# 3.net
KiCad netlist of a schematic drawn in Altium Designer
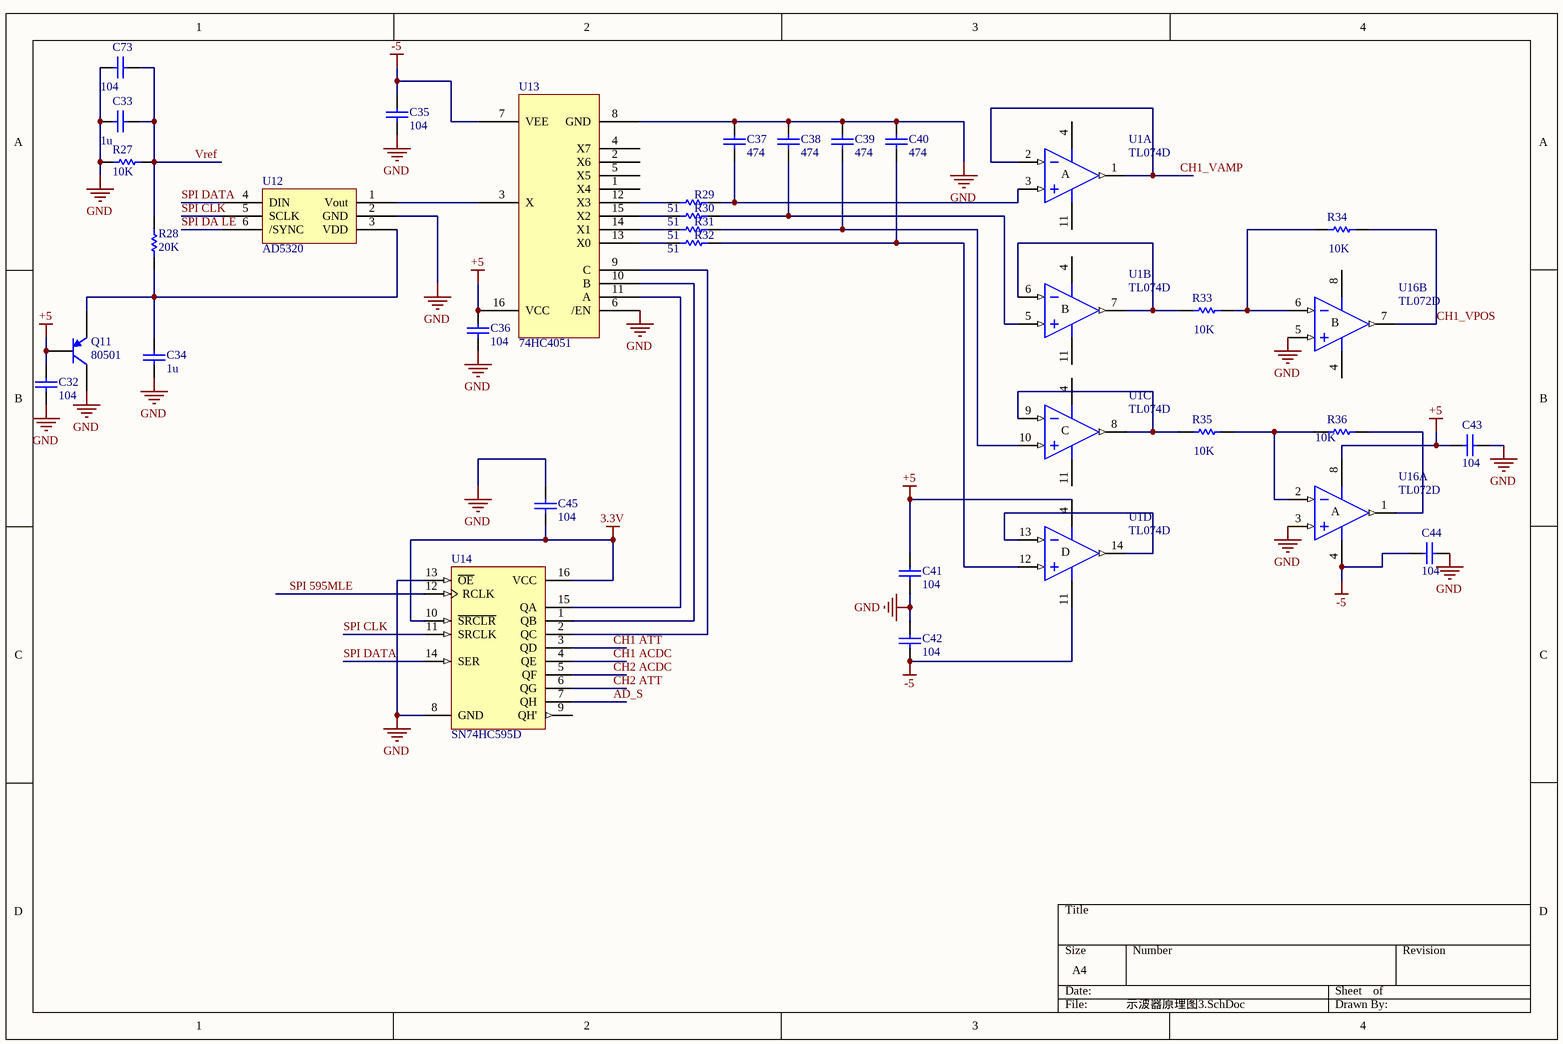
[diagram p0: 示波器原理图3.SchDoc]

(export (version "E")
  (design (tool "Eeschema 10.0.6"))
  (components
    (comp (ref "C32")
      (value "104")
      (footprint "PCBComponent_1")
      (description "Capacitor")
      (fields (field (name "PUBLISHER") "Altium Limited"))
      (libsource (lib "Miscellaneous Devices") (part "Cap"))
    )
    (comp (ref "C33")
      (value "1u")
      (footprint "PCBComponent_1")
      (description "Capacitor")
      (fields (field (name "PUBLISHER") "Altium Limited"))
      (libsource (lib "Miscellaneous Devices") (part "Cap"))
    )
    (comp (ref "C34")
      (value "1u")
      (footprint "PCBComponent_1")
      (description "Capacitor")
      (fields (field (name "PUBLISHER") "Altium Limited"))
      (libsource (lib "Miscellaneous Devices") (part "Cap"))
    )
    (comp (ref "C35")
      (value "104")
      (footprint "PCBComponent_1")
      (description "Capacitor")
      (fields (field (name "PUBLISHER") "Altium Limited"))
      (libsource (lib "Miscellaneous Devices") (part "Cap"))
    )
    (comp (ref "C36")
      (value "104")
      (footprint "PCBComponent_1")
      (description "Capacitor")
      (fields (field (name "PUBLISHER") "Altium Limited"))
      (libsource (lib "Miscellaneous Devices") (part "Cap"))
    )
    (comp (ref "C37")
      (value "474")
      (footprint "PCBComponent_1")
      (description "Capacitor")
      (fields (field (name "PUBLISHER") "Altium Limited"))
      (libsource (lib "Miscellaneous Devices") (part "Cap"))
    )
    (comp (ref "C38")
      (value "474")
      (footprint "PCBComponent_1")
      (description "Capacitor")
      (fields (field (name "PUBLISHER") "Altium Limited"))
      (libsource (lib "Miscellaneous Devices") (part "Cap"))
    )
    (comp (ref "C39")
      (value "474")
      (footprint "PCBComponent_1")
      (description "Capacitor")
      (fields (field (name "PUBLISHER") "Altium Limited"))
      (libsource (lib "Miscellaneous Devices") (part "Cap"))
    )
    (comp (ref "C40")
      (value "474")
      (footprint "PCBComponent_1")
      (description "Capacitor")
      (fields (field (name "PUBLISHER") "Altium Limited"))
      (libsource (lib "Miscellaneous Devices") (part "Cap"))
    )
    (comp (ref "C41")
      (value "104")
      (footprint "PCBComponent_1")
      (description "Capacitor")
      (fields (field (name "PUBLISHER") "Altium Limited"))
      (libsource (lib "Miscellaneous Devices") (part "Cap"))
    )
    (comp (ref "C42")
      (value "104")
      (footprint "PCBComponent_1")
      (description "Capacitor")
      (fields (field (name "PUBLISHER") "Altium Limited"))
      (libsource (lib "Miscellaneous Devices") (part "Cap"))
    )
    (comp (ref "C43")
      (value "104")
      (footprint "PCBComponent_1")
      (description "Capacitor")
      (fields (field (name "PUBLISHER") "Altium Limited"))
      (libsource (lib "Miscellaneous Devices") (part "Cap"))
    )
    (comp (ref "C44")
      (value "104")
      (footprint "PCBComponent_1")
      (description "Capacitor")
      (fields (field (name "PUBLISHER") "Altium Limited"))
      (libsource (lib "Miscellaneous Devices") (part "Cap"))
    )
    (comp (ref "C45")
      (value "104")
      (footprint "PCBComponent_1")
      (description "Capacitor")
      (fields (field (name "PUBLISHER") "Altium Limited"))
      (libsource (lib "Miscellaneous Devices") (part "Cap"))
    )
    (comp (ref "C73")
      (value "104")
      (footprint "PCBComponent_1")
      (description "Capacitor")
      (fields (field (name "PUBLISHER") "Altium Limited"))
      (libsource (lib "Miscellaneous Devices") (part "Cap"))
    )
    (comp (ref "Q11")
      (value "80501")
      (footprint "三极管贴片:PCBComponent_1")
      (description "PNP General Purpose Amplifier")
      (fields (field (name "PUBLISHER") "Altium Limited"))
      (libsource (lib "Miscellaneous Devices") (part "2N3906"))
    )
    (comp (ref "R27")
      (value "10K")
      (footprint "PCBComponent_1")
      (description "Resistor")
      (fields (field (name "PUBLISHER") "Altium Limited"))
      (libsource (lib "Miscellaneous Devices") (part "Res1"))
    )
    (comp (ref "R28")
      (value "20K")
      (footprint "PCBComponent_1")
      (description "Resistor")
      (fields (field (name "PUBLISHER") "Altium Limited"))
      (libsource (lib "Miscellaneous Devices") (part "Res1"))
    )
    (comp (ref "R29")
      (value "51")
      (footprint "2012[0805]")
      (description "Semiconductor Resistor")
      (fields (field (name "PUBLISHER") "Altium Limited"))
      (libsource (lib "Miscellaneous Devices") (part "Res Semi"))
    )
    (comp (ref "R30")
      (value "51")
      (footprint "2012[0805]")
      (description "Semiconductor Resistor")
      (fields (field (name "PUBLISHER") "Altium Limited"))
      (libsource (lib "Miscellaneous Devices") (part "Res Semi"))
    )
    (comp (ref "R31")
      (value "51")
      (footprint "2012[0805]")
      (description "Semiconductor Resistor")
      (fields (field (name "PUBLISHER") "Altium Limited"))
      (libsource (lib "Miscellaneous Devices") (part "Res Semi"))
    )
    (comp (ref "R32")
      (value "51")
      (footprint "2012[0805]")
      (description "Semiconductor Resistor")
      (fields (field (name "PUBLISHER") "Altium Limited"))
      (libsource (lib "Miscellaneous Devices") (part "Res Semi"))
    )
    (comp (ref "R33")
      (value "10K")
      (footprint "2012[0805]")
      (description "Semiconductor Resistor")
      (fields (field (name "PUBLISHER") "Altium Limited"))
      (libsource (lib "Miscellaneous Devices") (part "Res Semi"))
    )
    (comp (ref "R34")
      (value "10K")
      (footprint "2012[0805]")
      (description "Semiconductor Resistor")
      (fields (field (name "PUBLISHER") "Altium Limited"))
      (libsource (lib "Miscellaneous Devices") (part "Res Semi"))
    )
    (comp (ref "R35")
      (value "10K")
      (footprint "2012[0805]")
      (description "Semiconductor Resistor")
      (fields (field (name "PUBLISHER") "Altium Limited"))
      (libsource (lib "Miscellaneous Devices") (part "Res Semi"))
    )
    (comp (ref "R36")
      (value "10K")
      (footprint "2012[0805]")
      (description "Semiconductor Resistor")
      (fields (field (name "PUBLISHER") "Altium Limited"))
      (libsource (lib "Miscellaneous Devices") (part "Res Semi"))
    )
    (comp (ref "U1")
      (value "TL074D")
      (footprint "SOP127P600X175-14N")
      (description "Low-Noise JFET-Input Operational Amplifier")
      (fields (field (name "PUBLISHER") "Altium Limited"))
      (libsource (lib "TI Operational Amplifier") (part "TL074D"))
    )
    (comp (ref "U12")
      (value "AD5320")
      (footprint "SOT86P280X110-6N")
      (libsource (lib "AD5320") (part "Component_1"))
    )
    (comp (ref "U13")
      (value "74HC4051")
      (footprint "SOP127P600X175-16N")
      (libsource (lib "74HC4051") (part "Component_1"))
    )
    (comp (ref "U14")
      (value "SN74HC595D")
      (footprint "SOP127P600X175-16N")
      (description "8-Bit Shift Register with 3-State Output Registers")
      (fields (field (name "PUBLISHER") "Altium Limited"))
      (libsource (lib "TI Logic Register") (part "SN74HC595D"))
    )
    (comp (ref "U16")
      (value "TL072D")
      (footprint "SOP127P600X175-8N")
      (description "Low-Noise JFET-Input Operational Amplifier")
      (fields (field (name "PUBLISHER") "Altium Limited"))
      (libsource (lib "TI Operational Amplifier") (part "TL072D"))
    )
  )
  (nets
    (net (code "1") (name "+5") (class "Default")
      (node (ref "C32") (pin "2") (pinfunction "2_2") (pintype "passive"))
      (node (ref "C36") (pin "2") (pinfunction "2_2") (pintype "passive"))
      (node (ref "C41") (pin "1") (pinfunction "1_1") (pintype "passive"))
      (node (ref "C43") (pin "1") (pinfunction "1_1") (pintype "passive"))
      (node (ref "Q11") (pin "2") (pinfunction "B_2") (pintype "passive"))
      (node (ref "U1") (pin "4") (pinfunction "V+_4") (pintype "power_in"))
      (node (ref "U13") (pin "16") (pinfunction "VCC_16") (pintype "passive"))
      (node (ref "U16") (pin "8") (pinfunction "V+_8") (pintype "power_in"))
    )
    (net (code "2") (name "-5") (class "Default")
      (node (ref "C35") (pin "2") (pinfunction "2_2") (pintype "passive"))
      (node (ref "C42") (pin "2") (pinfunction "2_2") (pintype "passive"))
      (node (ref "C44") (pin "1") (pinfunction "1_1") (pintype "passive"))
      (node (ref "U1") (pin "11") (pinfunction "V-_11") (pintype "power_in"))
      (node (ref "U13") (pin "7") (pinfunction "VEE_7") (pintype "passive"))
      (node (ref "U16") (pin "4") (pinfunction "V-_4") (pintype "power_in"))
    )
    (net (code "3") (name "/AD_S") (class "Default")
      (node (ref "U14") (pin "7") (pinfunction "QH_7") (pintype "tri_state"))
    )
    (net (code "4") (name "/CH1 ACDC") (class "Default")
      (node (ref "U14") (pin "4") (pinfunction "QE_4") (pintype "tri_state"))
    )
    (net (code "5") (name "/CH1 ATT") (class "Default")
      (node (ref "U14") (pin "3") (pinfunction "QD_3") (pintype "tri_state"))
    )
    (net (code "6") (name "/CH1_VAMP") (class "Default")
      (node (ref "U1") (pin "1") (pinfunction "OUT_1") (pintype "output"))
      (node (ref "U1") (pin "2") (pinfunction "IN-_2") (pintype "input"))
    )
    (net (code "7") (name "/CH1_VPOS") (class "Default")
      (node (ref "R34") (pin "2") (pinfunction "2_2") (pintype "passive"))
      (node (ref "U16") (pin "7") (pinfunction "OUT_7") (pintype "output"))
    )
    (net (code "8") (name "/CH2 ACDC") (class "Default")
      (node (ref "U14") (pin "5") (pinfunction "QF_5") (pintype "tri_state"))
    )
    (net (code "9") (name "/CH2 ATT") (class "Default")
      (node (ref "U14") (pin "6") (pinfunction "QG_6") (pintype "tri_state"))
    )
    (net (code "10") (name "/SPI 595MLE") (class "Default")
      (node (ref "U14") (pin "12") (pinfunction "RCLK_12") (pintype "input"))
    )
    (net (code "11") (name "/SPI CLK") (class "Default")
      (node (ref "U12") (pin "5") (pinfunction "SCLK_5") (pintype "passive"))
      (node (ref "U14") (pin "11") (pinfunction "SRCLK_11") (pintype "input"))
    )
    (net (code "12") (name "/SPI DA LE") (class "Default")
      (node (ref "U12") (pin "6") (pinfunction "/SYNC_6") (pintype "passive"))
    )
    (net (code "13") (name "/SPI DATA") (class "Default")
      (node (ref "U12") (pin "4") (pinfunction "DIN_4") (pintype "passive"))
      (node (ref "U14") (pin "14") (pinfunction "SER_14") (pintype "input"))
    )
    (net (code "14") (name "/Vref") (class "Default")
      (node (ref "C33") (pin "2") (pinfunction "2_2") (pintype "passive"))
      (node (ref "C73") (pin "2") (pinfunction "2_2") (pintype "passive"))
      (node (ref "R27") (pin "1") (pinfunction "1_1") (pintype "passive"))
      (node (ref "R28") (pin "1") (pinfunction "1_1") (pintype "passive"))
    )
    (net (code "15") (name "3.3V") (class "Default")
      (node (ref "C45") (pin "1") (pinfunction "1_1") (pintype "passive"))
      (node (ref "U14") (pin "10") (pinfunction "~{SRCLR}_10") (pintype "input"))
      (node (ref "U14") (pin "16") (pinfunction "VCC_16") (pintype "power_in"))
    )
    (net (code "16") (name "GND") (class "Default")
      (node (ref "C32") (pin "1") (pinfunction "1_1") (pintype "passive"))
      (node (ref "C33") (pin "1") (pinfunction "1_1") (pintype "passive"))
      (node (ref "C34") (pin "1") (pinfunction "1_1") (pintype "passive"))
      (node (ref "C35") (pin "1") (pinfunction "1_1") (pintype "passive"))
      (node (ref "C36") (pin "1") (pinfunction "1_1") (pintype "passive"))
      (node (ref "C37") (pin "2") (pinfunction "2_2") (pintype "passive"))
      (node (ref "C38") (pin "2") (pinfunction "2_2") (pintype "passive"))
      (node (ref "C39") (pin "2") (pinfunction "2_2") (pintype "passive"))
      (node (ref "C40") (pin "2") (pinfunction "2_2") (pintype "passive"))
      (node (ref "C41") (pin "2") (pinfunction "2_2") (pintype "passive"))
      (node (ref "C42") (pin "1") (pinfunction "1_1") (pintype "passive"))
      (node (ref "C43") (pin "2") (pinfunction "2_2") (pintype "passive"))
      (node (ref "C44") (pin "2") (pinfunction "2_2") (pintype "passive"))
      (node (ref "C45") (pin "2") (pinfunction "2_2") (pintype "passive"))
      (node (ref "C73") (pin "1") (pinfunction "1_1") (pintype "passive"))
      (node (ref "Q11") (pin "3") (pinfunction "C_3") (pintype "passive"))
      (node (ref "R27") (pin "2") (pinfunction "2_2") (pintype "passive"))
      (node (ref "U12") (pin "2") (pinfunction "GND_2") (pintype "passive"))
      (node (ref "U13") (pin "6") (pinfunction "/EN_6") (pintype "passive"))
      (node (ref "U13") (pin "8") (pinfunction "GND_8") (pintype "passive"))
      (node (ref "U14") (pin "13") (pinfunction "~{OE}_13") (pintype "input"))
      (node (ref "U14") (pin "8") (pinfunction "GND_8") (pintype "power_in"))
      (node (ref "U16") (pin "3") (pinfunction "IN+_3") (pintype "input"))
      (node (ref "U16") (pin "5") (pinfunction "IN+_5") (pintype "input"))
    )
    (net (code "17") (name "Net-(Q11-E)") (class "Default")
      (node (ref "C34") (pin "2") (pinfunction "2_2") (pintype "passive"))
      (node (ref "Q11") (pin "1") (pinfunction "E_1") (pintype "passive"))
      (node (ref "R28") (pin "2") (pinfunction "2_2") (pintype "passive"))
      (node (ref "U12") (pin "3") (pinfunction "VDD_3") (pintype "passive"))
    )
    (net (code "18") (name "Net-(U1A-IN+)") (class "Default")
      (node (ref "C37") (pin "1") (pinfunction "1_1") (pintype "passive"))
      (node (ref "R29") (pin "2") (pinfunction "2_2") (pintype "passive"))
      (node (ref "U1") (pin "3") (pinfunction "IN+_3") (pintype "input"))
    )
    (net (code "19") (name "Net-(U1B-IN+)") (class "Default")
      (node (ref "C38") (pin "1") (pinfunction "1_1") (pintype "passive"))
      (node (ref "R30") (pin "2") (pinfunction "2_2") (pintype "passive"))
      (node (ref "U1") (pin "5") (pinfunction "IN+_5") (pintype "input"))
    )
    (net (code "20") (name "Net-(U1B-IN-)") (class "Default")
      (node (ref "R33") (pin "1") (pinfunction "1_1") (pintype "passive"))
      (node (ref "U1") (pin "6") (pinfunction "IN-_6") (pintype "input"))
      (node (ref "U1") (pin "7") (pinfunction "OUT_7") (pintype "output"))
    )
    (net (code "21") (name "Net-(U1C-IN+)") (class "Default")
      (node (ref "C39") (pin "1") (pinfunction "1_1") (pintype "passive"))
      (node (ref "R31") (pin "2") (pinfunction "2_2") (pintype "passive"))
      (node (ref "U1") (pin "10") (pinfunction "IN+_10") (pintype "input"))
    )
    (net (code "22") (name "Net-(U1C-IN-)") (class "Default")
      (node (ref "R35") (pin "1") (pinfunction "1_1") (pintype "passive"))
      (node (ref "U1") (pin "8") (pinfunction "OUT_8") (pintype "output"))
      (node (ref "U1") (pin "9") (pinfunction "IN-_9") (pintype "input"))
    )
    (net (code "23") (name "Net-(U1D-IN+)") (class "Default")
      (node (ref "C40") (pin "1") (pinfunction "1_1") (pintype "passive"))
      (node (ref "R32") (pin "2") (pinfunction "2_2") (pintype "passive"))
      (node (ref "U1") (pin "12") (pinfunction "IN+_12") (pintype "input"))
    )
    (net (code "24") (name "Net-(U1D-IN-)") (class "Default")
      (node (ref "U1") (pin "13") (pinfunction "IN-_13") (pintype "input"))
      (node (ref "U1") (pin "14") (pinfunction "OUT_14") (pintype "output"))
    )
    (net (code "25") (name "Net-(U12-Vout)") (class "Default")
      (node (ref "U12") (pin "1") (pinfunction "Vout_1") (pintype "passive"))
      (node (ref "U13") (pin "3") (pinfunction "X_3") (pintype "passive"))
    )
    (net (code "26") (name "Net-(U13-A)") (class "Default")
      (node (ref "U13") (pin "11") (pinfunction "A_11") (pintype "passive"))
      (node (ref "U14") (pin "15") (pinfunction "QA_15") (pintype "tri_state"))
    )
    (net (code "27") (name "Net-(U13-B)") (class "Default")
      (node (ref "U13") (pin "10") (pinfunction "B_10") (pintype "passive"))
      (node (ref "U14") (pin "1") (pinfunction "QB_1") (pintype "tri_state"))
    )
    (net (code "28") (name "Net-(U13-C)") (class "Default")
      (node (ref "U13") (pin "9") (pinfunction "C_9") (pintype "passive"))
      (node (ref "U14") (pin "2") (pinfunction "QC_2") (pintype "tri_state"))
    )
    (net (code "29") (name "Net-(U13-X0)") (class "Default")
      (node (ref "R32") (pin "1") (pinfunction "1_1") (pintype "passive"))
      (node (ref "U13") (pin "13") (pinfunction "X0_13") (pintype "passive"))
    )
    (net (code "30") (name "Net-(U13-X1)") (class "Default")
      (node (ref "R31") (pin "1") (pinfunction "1_1") (pintype "passive"))
      (node (ref "U13") (pin "14") (pinfunction "X1_14") (pintype "passive"))
    )
    (net (code "31") (name "Net-(U13-X2)") (class "Default")
      (node (ref "R30") (pin "1") (pinfunction "1_1") (pintype "passive"))
      (node (ref "U13") (pin "15") (pinfunction "X2_15") (pintype "passive"))
    )
    (net (code "32") (name "Net-(U13-X3)") (class "Default")
      (node (ref "R29") (pin "1") (pinfunction "1_1") (pintype "passive"))
      (node (ref "U13") (pin "12") (pinfunction "X3_12") (pintype "passive"))
    )
    (net (code "33") (name "Net-(U16A-IN-)") (class "Default")
      (node (ref "R35") (pin "2") (pinfunction "2_2") (pintype "passive"))
      (node (ref "R36") (pin "1") (pinfunction "1_1") (pintype "passive"))
      (node (ref "U16") (pin "2") (pinfunction "IN-_2") (pintype "input"))
    )
    (net (code "34") (name "Net-(U16A-OUT)") (class "Default")
      (node (ref "R36") (pin "2") (pinfunction "2_2") (pintype "passive"))
      (node (ref "U16") (pin "1") (pinfunction "OUT_1") (pintype "output"))
    )
    (net (code "35") (name "Net-(U16B-IN-)") (class "Default")
      (node (ref "R33") (pin "2") (pinfunction "2_2") (pintype "passive"))
      (node (ref "R34") (pin "1") (pinfunction "1_1") (pintype "passive"))
      (node (ref "U16") (pin "6") (pinfunction "IN-_6") (pintype "input"))
    )
    (net (code "36") (name "unconnected-(U1A-V+-Pad4)") (class "Default")
      (node (ref "U1") (pin "4") (pinfunction "V+_4") (pintype "power_in"))
    )
    (net (code "37") (name "unconnected-(U1A-V--Pad11)") (class "Default")
      (node (ref "U1") (pin "11") (pinfunction "V-_11") (pintype "power_in"))
    )
    (net (code "38") (name "unconnected-(U1B-V+-Pad4)") (class "Default")
      (node (ref "U1") (pin "4") (pinfunction "V+_4") (pintype "power_in"))
    )
    (net (code "39") (name "unconnected-(U1B-V--Pad11)") (class "Default")
      (node (ref "U1") (pin "11") (pinfunction "V-_11") (pintype "power_in"))
    )
    (net (code "40") (name "unconnected-(U1C-V+-Pad4)") (class "Default")
      (node (ref "U1") (pin "4") (pinfunction "V+_4") (pintype "power_in"))
    )
    (net (code "41") (name "unconnected-(U1C-V--Pad11)") (class "Default")
      (node (ref "U1") (pin "11") (pinfunction "V-_11") (pintype "power_in"))
    )
    (net (code "42") (name "unconnected-(U13-X4-Pad1)") (class "Default")
      (node (ref "U13") (pin "1") (pinfunction "X4_1") (pintype "passive"))
    )
    (net (code "43") (name "unconnected-(U13-X5-Pad5)") (class "Default")
      (node (ref "U13") (pin "5") (pinfunction "X5_5") (pintype "passive"))
    )
    (net (code "44") (name "unconnected-(U13-X6-Pad2)") (class "Default")
      (node (ref "U13") (pin "2") (pinfunction "X6_2") (pintype "passive"))
    )
    (net (code "45") (name "unconnected-(U13-X7-Pad4)") (class "Default")
      (node (ref "U13") (pin "4") (pinfunction "X7_4") (pintype "passive"))
    )
    (net (code "46") (name "unconnected-(U14-QH'-Pad9)") (class "Default")
      (node (ref "U14") (pin "9") (pinfunction "QH'_9") (pintype "output"))
    )
    (net (code "47") (name "unconnected-(U16B-V+-Pad8)") (class "Default")
      (node (ref "U16") (pin "8") (pinfunction "V+_8") (pintype "power_in"))
    )
    (net (code "48") (name "unconnected-(U16B-V--Pad4)") (class "Default")
      (node (ref "U16") (pin "4") (pinfunction "V-_4") (pintype "power_in"))
    )
  )
)
